# ZYNQ400-MIO.net
KiCad netlist of a schematic drawn in Altium Designer
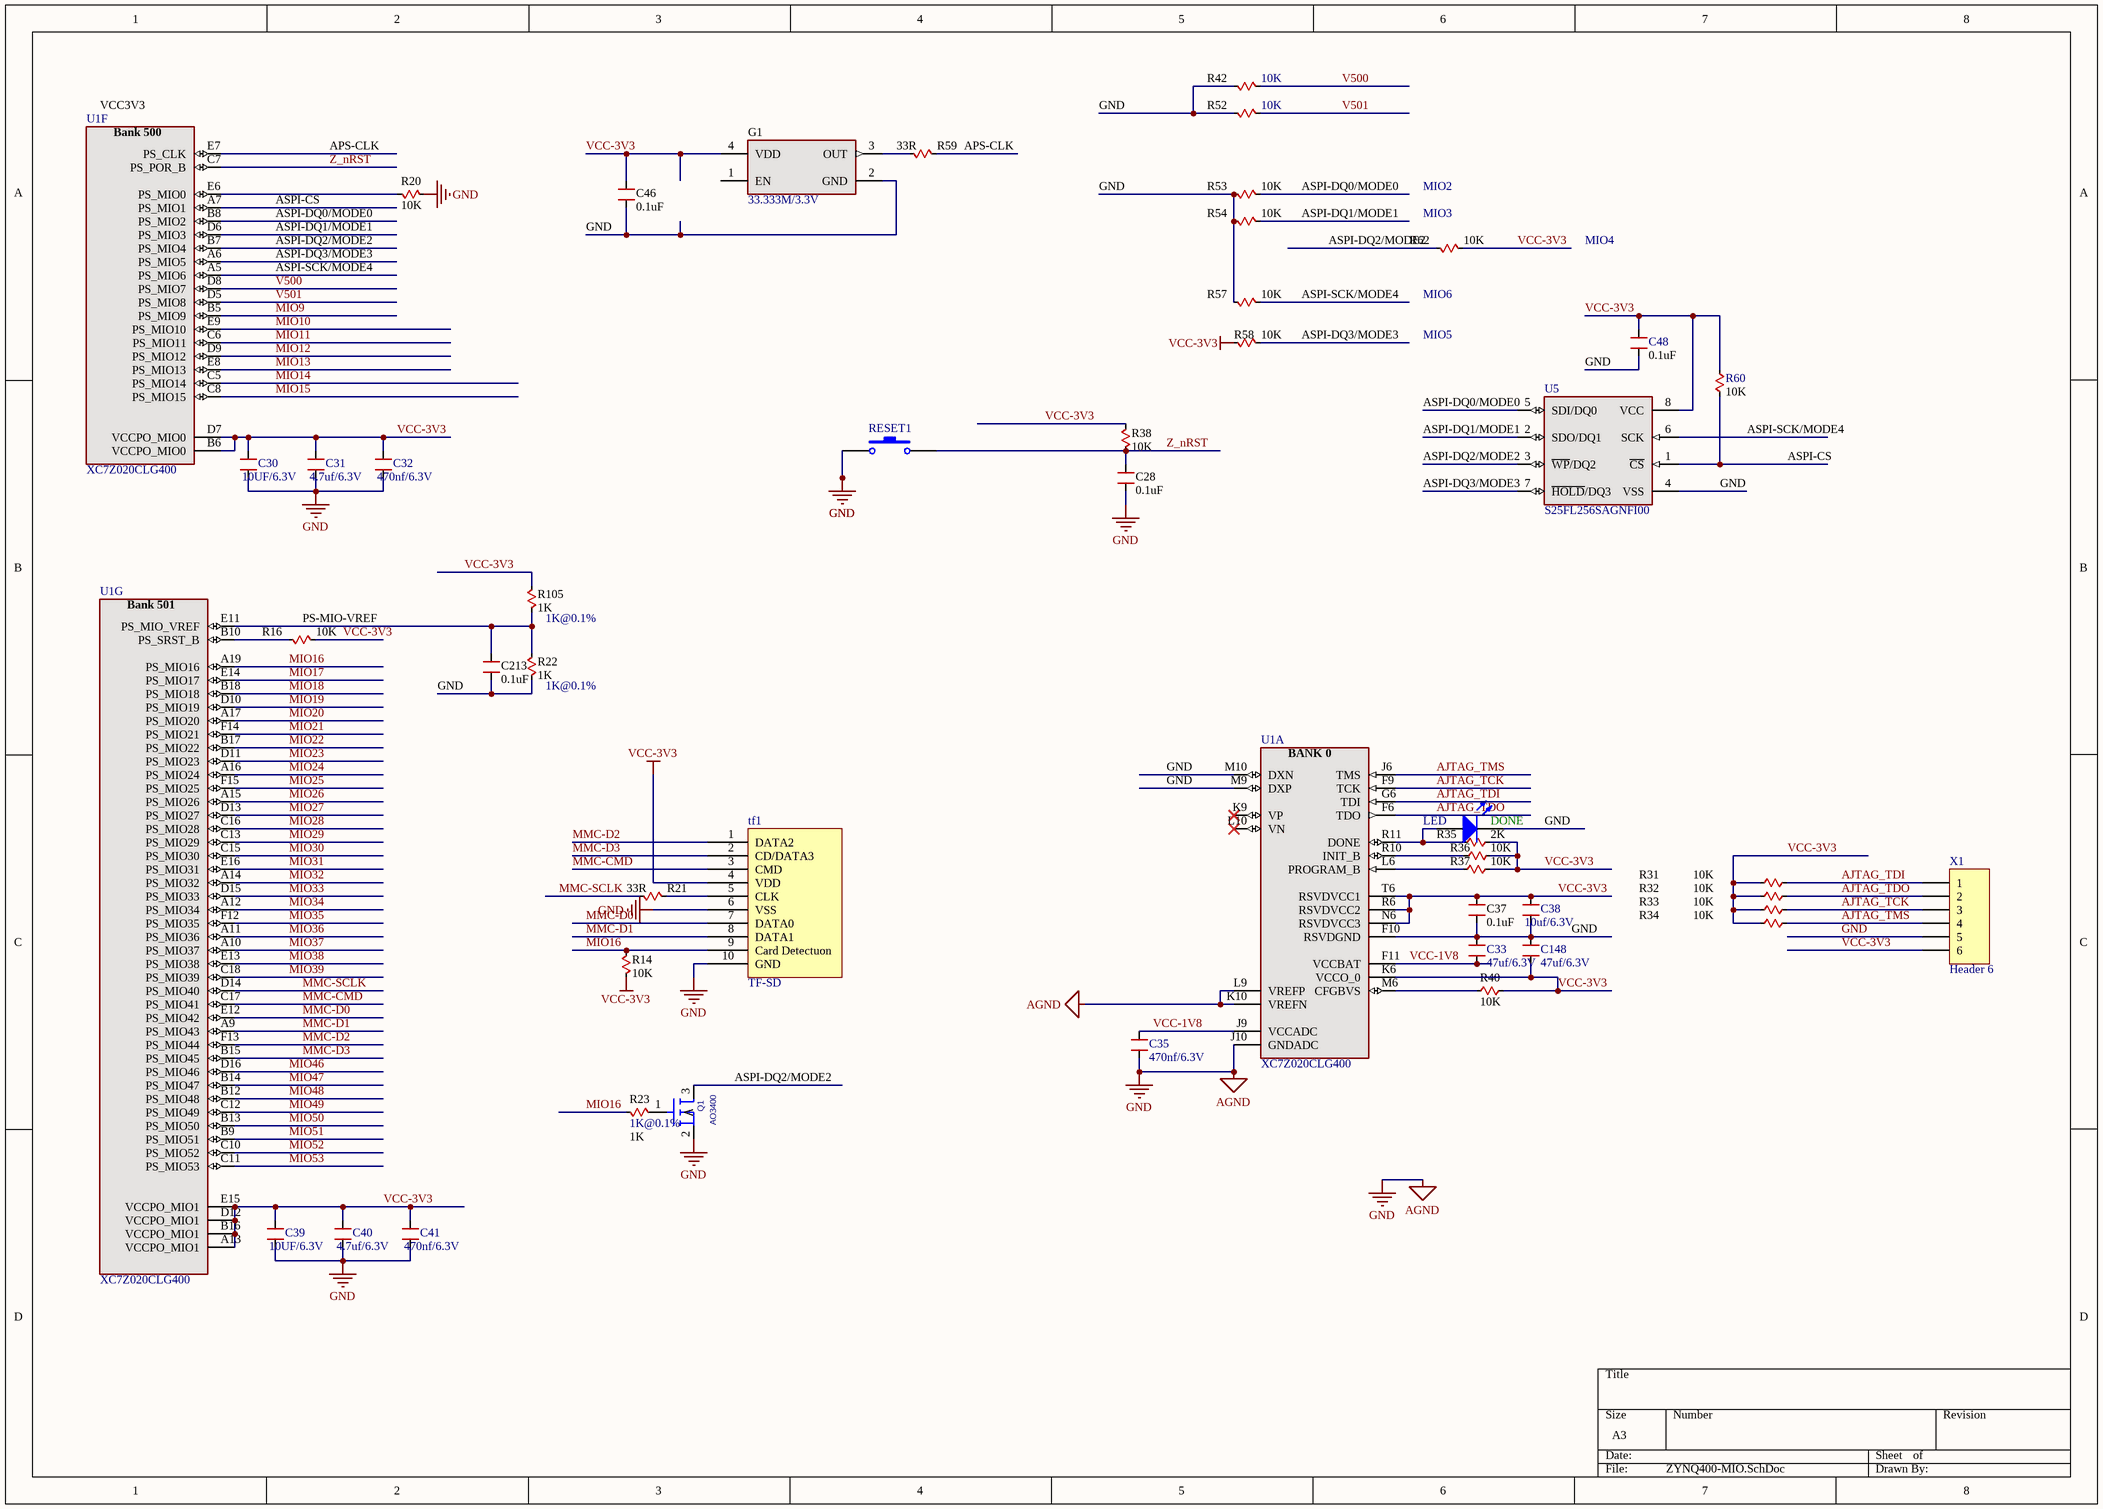
[diagram p0: ZYNQ400-MIO.SchDoc]

(export (version "E")
  (design (tool "Eeschema 10.0.6"))
  (components
    (comp (ref "C28")
      (value "0.1uF")
      (footprint "0402")
      (description "Generic Capacitor")
      (fields (field (name "Comment") "0.1UF"))
      (libsource (lib "Digilent") (part "CAPACITOR"))
    )
    (comp (ref "C30")
      (value "10UF/6.3V")
      (footprint "0402")
      (description "Generic Capacitor")
      (libsource (lib "Digilent") (part "CAPACITOR"))
    )
    (comp (ref "C31")
      (value "4.7uf/6.3V")
      (footprint "0402")
      (description "Generic Capacitor")
      (libsource (lib "Digilent") (part "CAPACITOR"))
    )
    (comp (ref "C32")
      (value "470nf/6.3V")
      (footprint "0402")
      (description "Generic Capacitor")
      (libsource (lib "Digilent") (part "CAPACITOR"))
    )
    (comp (ref "C33")
      (value "47uf/6.3V")
      (footprint "0402")
      (description "Generic Capacitor")
      (libsource (lib "Digilent") (part "CAPACITOR"))
    )
    (comp (ref "C35")
      (value "470nf/6.3V")
      (footprint "0402")
      (description "Generic Capacitor")
      (libsource (lib "Digilent") (part "CAPACITOR"))
    )
    (comp (ref "C37")
      (value "0.1uF")
      (footprint "0402")
      (description "Generic Capacitor")
      (fields (field (name "Comment") "0.1UF"))
      (libsource (lib "Digilent") (part "CAPACITOR"))
    )
    (comp (ref "C38")
      (value "10uf/6.3V")
      (footprint "0603")
      (description "Generic Capacitor")
      (libsource (lib "Digilent") (part "CAPACITOR"))
    )
    (comp (ref "C39")
      (value "10UF/6.3V")
      (footprint "0402")
      (description "Generic Capacitor")
      (libsource (lib "Digilent") (part "CAPACITOR"))
    )
    (comp (ref "C40")
      (value "4.7uf/6.3V")
      (footprint "0402")
      (description "Generic Capacitor")
      (libsource (lib "Digilent") (part "CAPACITOR"))
    )
    (comp (ref "C41")
      (value "470nf/6.3V")
      (footprint "0402")
      (description "Generic Capacitor")
      (libsource (lib "Digilent") (part "CAPACITOR"))
    )
    (comp (ref "C46")
      (value "0.1uF")
      (footprint "0402")
      (description "Generic Capacitor")
      (fields (field (name "Comment") "0.1UF"))
      (libsource (lib "Digilent") (part "CAPACITOR"))
    )
    (comp (ref "C48")
      (value "0.1uF")
      (footprint "0402")
      (description "Generic Capacitor")
      (fields (field (name "Comment") "0.1UF"))
      (libsource (lib "Digilent") (part "CAPACITOR"))
    )
    (comp (ref "C148")
      (value "47uf/6.3V")
      (footprint "0402")
      (description "Generic Capacitor")
      (libsource (lib "Digilent") (part "CAPACITOR"))
    )
    (comp (ref "C213")
      (value "0.1uF")
      (footprint "0402")
      (description "Generic Capacitor")
      (libsource (lib "Digilent") (part "CAPACITOR"))
    )
    (comp (ref "DONE")
      (value "LED")
      (footprint "D0402")
      (description "Typical INFRARED GaAs LED")
      (fields (field (name "PUBLISHER") "Altium Limited"))
      (libsource (lib "Miscellaneous Devices") (part "LED0"))
    )
    (comp (ref "G1")
      (value "33.333M/3.3V")
      (footprint "3.2*2.5")
      (description "3.3V HCMOS Oscillator")
      (fields (field (name "MANUFACTURER") "Fox Electronics"))
      (libsource (lib "Digilent") (part "FXO-HC5"))
    )
    (comp (ref "Q1") (value "AO3400") (footprint "SOT23") (libsource (lib "ZYNQ领航者底板") (part "AO3400")))
    (comp (ref "R14")
      (value "10K")
      (footprint "0402")
      (description "Generic Resistor")
      (libsource (lib "Digilent") (part "RESISTOR"))
    )
    (comp (ref "R16")
      (value "10K")
      (footprint "0402")
      (description "Generic Resistor")
      (libsource (lib "Digilent") (part "RESISTOR"))
    )
    (comp (ref "R20")
      (value "10K")
      (footprint "0402")
      (description "Generic Resistor")
      (libsource (lib "Digilent") (part "RESISTOR"))
    )
    (comp (ref "R21")
      (value "33R")
      (footprint "0402")
      (description "Generic Resistor")
      (libsource (lib "Digilent") (part "RESISTOR"))
    )
    (comp (ref "R22")
      (value "1K@0.1%")
      (footprint "0402")
      (description "Generic Resistor")
      (fields (field (name "ALTIUM_VALUE") "1K"))
      (libsource (lib "Digilent") (part "RESISTOR"))
    )
    (comp (ref "R23")
      (value "1K@0.1%")
      (footprint "0402")
      (description "Generic Resistor")
      (fields (field (name "ALTIUM_VALUE") "1K"))
      (libsource (lib "Digilent") (part "RESISTOR"))
    )
    (comp (ref "R31")
      (value "10K")
      (footprint "0402")
      (description "Generic Resistor")
      (libsource (lib "Digilent") (part "RESISTOR"))
    )
    (comp (ref "R32")
      (value "10K")
      (footprint "0402")
      (description "Generic Resistor")
      (libsource (lib "Digilent") (part "RESISTOR"))
    )
    (comp (ref "R33")
      (value "10K")
      (footprint "0402")
      (description "Generic Resistor")
      (libsource (lib "Digilent") (part "RESISTOR"))
    )
    (comp (ref "R34")
      (value "10K")
      (footprint "0402")
      (description "Generic Resistor")
      (libsource (lib "Digilent") (part "RESISTOR"))
    )
    (comp (ref "R35")
      (value "2K")
      (footprint "0402")
      (description "Generic Resistor")
      (fields (field (name "Comment") "1K"))
      (libsource (lib "Digilent") (part "RESISTOR"))
    )
    (comp (ref "R36")
      (value "10K")
      (footprint "0402")
      (description "Generic Resistor")
      (libsource (lib "Digilent") (part "RESISTOR"))
    )
    (comp (ref "R37")
      (value "10K")
      (footprint "0402")
      (description "Generic Resistor")
      (libsource (lib "Digilent") (part "RESISTOR"))
    )
    (comp (ref "R38")
      (value "10K")
      (footprint "0402")
      (description "Generic Resistor")
      (libsource (lib "Digilent") (part "RESISTOR"))
    )
    (comp (ref "R40")
      (value "10K")
      (footprint "0402")
      (description "Generic Resistor")
      (libsource (lib "Digilent") (part "RESISTOR"))
    )
    (comp (ref "R42")
      (value "10K")
      (footprint "0402")
      (description "Generic Resistor")
      (libsource (lib "Digilent") (part "RESISTOR"))
    )
    (comp (ref "R52")
      (value "10K")
      (footprint "0402")
      (description "Generic Resistor")
      (libsource (lib "Digilent") (part "RESISTOR"))
    )
    (comp (ref "R53")
      (value "10K")
      (footprint "0402")
      (description "Generic Resistor")
      (libsource (lib "Digilent") (part "RESISTOR"))
    )
    (comp (ref "R54")
      (value "10K")
      (footprint "0402")
      (description "Generic Resistor")
      (libsource (lib "Digilent") (part "RESISTOR"))
    )
    (comp (ref "R57")
      (value "10K")
      (footprint "0402")
      (description "Generic Resistor")
      (libsource (lib "Digilent") (part "RESISTOR"))
    )
    (comp (ref "R58")
      (value "10K")
      (footprint "0402")
      (description "Generic Resistor")
      (libsource (lib "Digilent") (part "RESISTOR"))
    )
    (comp (ref "R59")
      (value "33R")
      (footprint "0402")
      (description "Generic Resistor")
      (libsource (lib "Digilent") (part "RESISTOR"))
    )
    (comp (ref "R60")
      (value "10K")
      (footprint "0402")
      (description "Generic Resistor")
      (libsource (lib "Digilent") (part "RESISTOR"))
    )
    (comp (ref "R62")
      (value "10K")
      (footprint "0402")
      (description "Generic Resistor")
      (libsource (lib "Digilent") (part "RESISTOR"))
    )
    (comp (ref "R105")
      (value "1K@0.1%")
      (footprint "0402")
      (description "Generic Resistor")
      (fields (field (name "ALTIUM_VALUE") "1K"))
      (libsource (lib "Digilent") (part "RESISTOR"))
    )
    (comp (ref "RESET1")
      (value "SW-PB")
      (footprint "micro button_2_SMD")
      (description "Switch")
      (fields (field (name "PUBLISHER") "Altium Limited"))
      (libsource (lib "M4(3333)") (part "SW-PB"))
    )
    (comp (ref "tf1") (value "TF-SD") (footprint "TF") (libsource (lib "M4(3333)") (part "TF-SD")))
    (comp (ref "U1")
      (value "XC7Z020CLG400")
      (footprint "CLG400")
      (description "Zynq 7000 FPGA 20 Die, in a CSG 484 Package")
      (fields (field (name "MANUFACTURER") "Xilinx"))
      (libsource (lib "gjws") (part "XC7Z020-CLG400"))
    )
    (comp (ref "U5")
      (value "S25FL256SAGNFI00")
      (footprint "MLP8")
      (description "Serial Flash Memory, 16Mbit, Low Voltage, 50MHz SPI Bus Interface")
      (fields (field (name "MANUFACTURER") "Spansion"))
      (libsource (lib "Digilent") (part "N25Q12-F8"))
    )
    (comp (ref "X1")
      (value "Header 6")
      (footprint "HDR1X6")
      (description "Header, 6-Pin")
      (fields (field (name "PUBLISHER") "Altium Limited"))
      (libsource (lib "Miscellaneous Connectors") (part "Header 6"))
    )
  )
  (nets
    (net (code "1") (name "/AJTAG_TCK") (class "Default")
      (node (ref "R33") (pin "2") (pinfunction "2_2") (pintype "passive"))
      (node (ref "U1") (pin "F9") (pinfunction "TCK_F9") (pintype "input"))
      (node (ref "X1") (pin "3") (pinfunction "3_3") (pintype "passive"))
    )
    (net (code "2") (name "/AJTAG_TDI") (class "Default")
      (node (ref "R31") (pin "2") (pinfunction "2_2") (pintype "passive"))
      (node (ref "U1") (pin "G6") (pinfunction "TDI_G6") (pintype "input"))
      (node (ref "X1") (pin "1") (pinfunction "1_1") (pintype "passive"))
    )
    (net (code "3") (name "/AJTAG_TDO") (class "Default")
      (node (ref "R32") (pin "2") (pinfunction "2_2") (pintype "passive"))
      (node (ref "U1") (pin "F6") (pinfunction "TDO_F6") (pintype "output"))
      (node (ref "X1") (pin "2") (pinfunction "2_2") (pintype "passive"))
    )
    (net (code "4") (name "/AJTAG_TMS") (class "Default")
      (node (ref "R34") (pin "2") (pinfunction "2_2") (pintype "passive"))
      (node (ref "U1") (pin "J6") (pinfunction "TMS_J6") (pintype "input"))
      (node (ref "X1") (pin "4") (pinfunction "4_4") (pintype "passive"))
    )
    (net (code "5") (name "/APS-CLK") (class "Default")
      (node (ref "R59") (pin "2") (pinfunction "2_2") (pintype "passive"))
      (node (ref "U1") (pin "E7") (pinfunction "PS_CLK_E7") (pintype "bidirectional"))
    )
    (net (code "6") (name "/ASPI-CS") (class "Default")
      (node (ref "R60") (pin "2") (pinfunction "2_2") (pintype "passive"))
      (node (ref "U1") (pin "A7") (pinfunction "PS_MIO1_A7") (pintype "bidirectional"))
      (node (ref "U5") (pin "1") (pinfunction "~{CS}_1") (pintype "input"))
    )
    (net (code "7") (name "/ASPI-DQ0{slash}MODE0") (class "Default")
      (node (ref "R53") (pin "2") (pinfunction "2_2") (pintype "passive"))
      (node (ref "U1") (pin "B8") (pinfunction "PS_MIO2_B8") (pintype "bidirectional"))
      (node (ref "U5") (pin "5") (pinfunction "SDI/DQ0_5") (pintype "bidirectional"))
    )
    (net (code "8") (name "/ASPI-DQ1{slash}MODE1") (class "Default")
      (node (ref "R54") (pin "2") (pinfunction "2_2") (pintype "passive"))
      (node (ref "U1") (pin "D6") (pinfunction "PS_MIO3_D6") (pintype "bidirectional"))
      (node (ref "U5") (pin "2") (pinfunction "SDO/DQ1_2") (pintype "bidirectional"))
    )
    (net (code "9") (name "/ASPI-DQ2{slash}MODE2") (class "Default")
      (node (ref "Q1") (pin "3") (pinfunction "D_3") (pintype "passive"))
      (node (ref "R62") (pin "1") (pinfunction "1_1") (pintype "passive"))
      (node (ref "U1") (pin "B7") (pinfunction "PS_MIO4_B7") (pintype "bidirectional"))
      (node (ref "U5") (pin "3") (pinfunction "~{WP}/DQ2_3") (pintype "bidirectional"))
    )
    (net (code "10") (name "/ASPI-DQ3{slash}MODE3") (class "Default")
      (node (ref "R58") (pin "2") (pinfunction "2_2") (pintype "passive"))
      (node (ref "U1") (pin "A6") (pinfunction "PS_MIO5_A6") (pintype "bidirectional"))
      (node (ref "U5") (pin "7") (pinfunction "~{HOLD}/DQ3_7") (pintype "bidirectional"))
    )
    (net (code "11") (name "/ASPI-SCK{slash}MODE4") (class "Default")
      (node (ref "R57") (pin "2") (pinfunction "2_2") (pintype "passive"))
      (node (ref "U1") (pin "A5") (pinfunction "PS_MIO6_A5") (pintype "bidirectional"))
      (node (ref "U5") (pin "6") (pinfunction "SCK_6") (pintype "input"))
    )
    (net (code "12") (name "/MIO9") (class "Default")
      (node (ref "U1") (pin "B5") (pinfunction "PS_MIO9_B5") (pintype "bidirectional"))
    )
    (net (code "13") (name "/MIO10") (class "Default")
      (node (ref "U1") (pin "E9") (pinfunction "PS_MIO10_E9") (pintype "bidirectional"))
    )
    (net (code "14") (name "/MIO11") (class "Default")
      (node (ref "U1") (pin "C6") (pinfunction "PS_MIO11_C6") (pintype "bidirectional"))
    )
    (net (code "15") (name "/MIO12") (class "Default")
      (node (ref "U1") (pin "D9") (pinfunction "PS_MIO12_D9") (pintype "bidirectional"))
    )
    (net (code "16") (name "/MIO13") (class "Default")
      (node (ref "U1") (pin "E8") (pinfunction "PS_MIO13_E8") (pintype "bidirectional"))
    )
    (net (code "17") (name "/MIO14") (class "Default")
      (node (ref "U1") (pin "C5") (pinfunction "PS_MIO14_C5") (pintype "bidirectional"))
    )
    (net (code "18") (name "/MIO15") (class "Default")
      (node (ref "U1") (pin "C8") (pinfunction "PS_MIO15_C8") (pintype "bidirectional"))
    )
    (net (code "19") (name "/MIO16") (class "Default")
      (node (ref "R14") (pin "2") (pinfunction "2_2") (pintype "passive"))
      (node (ref "R23") (pin "1") (pinfunction "1_1") (pintype "passive"))
      (node (ref "U1") (pin "A19") (pinfunction "PS_MIO16_A19") (pintype "bidirectional"))
      (node (ref "tf1") (pin "9") (pinfunction "Card_Detectuon_9") (pintype "passive"))
    )
    (net (code "20") (name "/MIO17") (class "Default")
      (node (ref "U1") (pin "E14") (pinfunction "PS_MIO17_E14") (pintype "bidirectional"))
    )
    (net (code "21") (name "/MIO18") (class "Default")
      (node (ref "U1") (pin "B18") (pinfunction "PS_MIO18_B18") (pintype "bidirectional"))
    )
    (net (code "22") (name "/MIO19") (class "Default")
      (node (ref "U1") (pin "D10") (pinfunction "PS_MIO19_D10") (pintype "bidirectional"))
    )
    (net (code "23") (name "/MIO20") (class "Default")
      (node (ref "U1") (pin "A17") (pinfunction "PS_MIO20_A17") (pintype "bidirectional"))
    )
    (net (code "24") (name "/MIO21") (class "Default")
      (node (ref "U1") (pin "F14") (pinfunction "PS_MIO21_F14") (pintype "bidirectional"))
    )
    (net (code "25") (name "/MIO22") (class "Default")
      (node (ref "U1") (pin "B17") (pinfunction "PS_MIO22_B17") (pintype "bidirectional"))
    )
    (net (code "26") (name "/MIO23") (class "Default")
      (node (ref "U1") (pin "D11") (pinfunction "PS_MIO23_D11") (pintype "bidirectional"))
    )
    (net (code "27") (name "/MIO24") (class "Default")
      (node (ref "U1") (pin "A16") (pinfunction "PS_MIO24_A16") (pintype "bidirectional"))
    )
    (net (code "28") (name "/MIO25") (class "Default")
      (node (ref "U1") (pin "F15") (pinfunction "PS_MIO25_F15") (pintype "bidirectional"))
    )
    (net (code "29") (name "/MIO26") (class "Default")
      (node (ref "U1") (pin "A15") (pinfunction "PS_MIO26_A15") (pintype "bidirectional"))
    )
    (net (code "30") (name "/MIO27") (class "Default")
      (node (ref "U1") (pin "D13") (pinfunction "PS_MIO27_D13") (pintype "bidirectional"))
    )
    (net (code "31") (name "/MIO28") (class "Default")
      (node (ref "U1") (pin "C16") (pinfunction "PS_MIO28_C16") (pintype "bidirectional"))
    )
    (net (code "32") (name "/MIO29") (class "Default")
      (node (ref "U1") (pin "C13") (pinfunction "PS_MIO29_C13") (pintype "bidirectional"))
    )
    (net (code "33") (name "/MIO30") (class "Default")
      (node (ref "U1") (pin "C15") (pinfunction "PS_MIO30_C15") (pintype "bidirectional"))
    )
    (net (code "34") (name "/MIO31") (class "Default")
      (node (ref "U1") (pin "E16") (pinfunction "PS_MIO31_E16") (pintype "bidirectional"))
    )
    (net (code "35") (name "/MIO32") (class "Default")
      (node (ref "U1") (pin "A14") (pinfunction "PS_MIO32_A14") (pintype "bidirectional"))
    )
    (net (code "36") (name "/MIO33") (class "Default")
      (node (ref "U1") (pin "D15") (pinfunction "PS_MIO33_D15") (pintype "bidirectional"))
    )
    (net (code "37") (name "/MIO34") (class "Default")
      (node (ref "U1") (pin "A12") (pinfunction "PS_MIO34_A12") (pintype "bidirectional"))
    )
    (net (code "38") (name "/MIO35") (class "Default")
      (node (ref "U1") (pin "F12") (pinfunction "PS_MIO35_F12") (pintype "bidirectional"))
    )
    (net (code "39") (name "/MIO36") (class "Default")
      (node (ref "U1") (pin "A11") (pinfunction "PS_MIO36_A11") (pintype "bidirectional"))
    )
    (net (code "40") (name "/MIO37") (class "Default")
      (node (ref "U1") (pin "A10") (pinfunction "PS_MIO37_A10") (pintype "bidirectional"))
    )
    (net (code "41") (name "/MIO38") (class "Default")
      (node (ref "U1") (pin "E13") (pinfunction "PS_MIO38_E13") (pintype "bidirectional"))
    )
    (net (code "42") (name "/MIO39") (class "Default")
      (node (ref "U1") (pin "C18") (pinfunction "PS_MIO39_C18") (pintype "bidirectional"))
    )
    (net (code "43") (name "/MIO46") (class "Default")
      (node (ref "U1") (pin "D16") (pinfunction "PS_MIO46_D16") (pintype "bidirectional"))
    )
    (net (code "44") (name "/MIO47") (class "Default")
      (node (ref "U1") (pin "B14") (pinfunction "PS_MIO47_B14") (pintype "bidirectional"))
    )
    (net (code "45") (name "/MIO48") (class "Default")
      (node (ref "U1") (pin "B12") (pinfunction "PS_MIO48_B12") (pintype "bidirectional"))
    )
    (net (code "46") (name "/MIO49") (class "Default")
      (node (ref "U1") (pin "C12") (pinfunction "PS_MIO49_C12") (pintype "bidirectional"))
    )
    (net (code "47") (name "/MIO50") (class "Default")
      (node (ref "U1") (pin "B13") (pinfunction "PS_MIO50_B13") (pintype "bidirectional"))
    )
    (net (code "48") (name "/MIO51") (class "Default")
      (node (ref "U1") (pin "B9") (pinfunction "PS_MIO51_B9") (pintype "bidirectional"))
    )
    (net (code "49") (name "/MIO52") (class "Default")
      (node (ref "U1") (pin "C10") (pinfunction "PS_MIO52_C10") (pintype "bidirectional"))
    )
    (net (code "50") (name "/MIO53") (class "Default")
      (node (ref "U1") (pin "C11") (pinfunction "PS_MIO53_C11") (pintype "bidirectional"))
    )
    (net (code "51") (name "/MMC-CMD") (class "Default")
      (node (ref "U1") (pin "C17") (pinfunction "PS_MIO41_C17") (pintype "bidirectional"))
      (node (ref "tf1") (pin "3") (pinfunction "CMD_3") (pintype "passive"))
    )
    (net (code "52") (name "/MMC-D0") (class "Default")
      (node (ref "U1") (pin "E12") (pinfunction "PS_MIO42_E12") (pintype "bidirectional"))
      (node (ref "tf1") (pin "7") (pinfunction "DATA0_7") (pintype "passive"))
    )
    (net (code "53") (name "/MMC-D1") (class "Default")
      (node (ref "U1") (pin "A9") (pinfunction "PS_MIO43_A9") (pintype "bidirectional"))
      (node (ref "tf1") (pin "8") (pinfunction "DATA1_8") (pintype "passive"))
    )
    (net (code "54") (name "/MMC-D2") (class "Default")
      (node (ref "U1") (pin "F13") (pinfunction "PS_MIO44_F13") (pintype "bidirectional"))
      (node (ref "tf1") (pin "1") (pinfunction "DATA2_1") (pintype "passive"))
    )
    (net (code "55") (name "/MMC-D3") (class "Default")
      (node (ref "U1") (pin "B15") (pinfunction "PS_MIO45_B15") (pintype "bidirectional"))
      (node (ref "tf1") (pin "2") (pinfunction "CD/DATA3_2") (pintype "passive"))
    )
    (net (code "56") (name "/MMC-SCLK") (class "Default")
      (node (ref "R21") (pin "1") (pinfunction "1_1") (pintype "passive"))
      (node (ref "U1") (pin "D14") (pinfunction "PS_MIO40_D14") (pintype "bidirectional"))
    )
    (net (code "57") (name "/PS-MIO-VREF") (class "Default")
      (node (ref "C213") (pin "1") (pinfunction "1_1") (pintype "passive"))
      (node (ref "R105") (pin "2") (pinfunction "2_2") (pintype "passive"))
      (node (ref "R22") (pin "1") (pinfunction "1_1") (pintype "passive"))
      (node (ref "U1") (pin "E11") (pinfunction "PS_MIO_VREF_E11") (pintype "bidirectional"))
    )
    (net (code "58") (name "/V500") (class "Default")
      (node (ref "R42") (pin "2") (pinfunction "2_2") (pintype "passive"))
      (node (ref "U1") (pin "D8") (pinfunction "PS_MIO7_D8") (pintype "bidirectional"))
    )
    (net (code "59") (name "/V501") (class "Default")
      (node (ref "R52") (pin "2") (pinfunction "2_2") (pintype "passive"))
      (node (ref "U1") (pin "D5") (pinfunction "PS_MIO8_D5") (pintype "bidirectional"))
    )
    (net (code "60") (name "/VCC-1V8") (class "Default")
      (node (ref "C33") (pin "1") (pinfunction "1_1") (pintype "passive"))
      (node (ref "C35") (pin "1") (pinfunction "1_1") (pintype "passive"))
      (node (ref "U1") (pin "F11") (pinfunction "VCCBAT_F11") (pintype "passive"))
      (node (ref "U1") (pin "J9") (pinfunction "VCCADC_J9") (pintype "passive"))
    )
    (net (code "61") (name "/Z_nRST") (class "Default")
      (node (ref "C28") (pin "1") (pinfunction "1_1") (pintype "passive"))
      (node (ref "R38") (pin "1") (pinfunction "1_1") (pintype "passive"))
      (node (ref "RESET1") (pin "2") (pinfunction "2_2") (pintype "passive"))
      (node (ref "U1") (pin "C7") (pinfunction "PS_POR_B_C7") (pintype "bidirectional"))
    )
    (net (code "62") (name "AGND") (class "Default")
      (node (ref "C148") (pin "2") (pinfunction "2_2") (pintype "passive"))
      (node (ref "C213") (pin "2") (pinfunction "2_2") (pintype "passive"))
      (node (ref "C28") (pin "2") (pinfunction "2_2") (pintype "passive"))
      (node (ref "C30") (pin "2") (pinfunction "2_2") (pintype "passive"))
      (node (ref "C31") (pin "2") (pinfunction "2_2") (pintype "passive"))
      (node (ref "C32") (pin "2") (pinfunction "2_2") (pintype "passive"))
      (node (ref "C33") (pin "2") (pinfunction "2_2") (pintype "passive"))
      (node (ref "C35") (pin "2") (pinfunction "2_2") (pintype "passive"))
      (node (ref "C37") (pin "2") (pinfunction "2_2") (pintype "passive"))
      (node (ref "C38") (pin "2") (pinfunction "2_2") (pintype "passive"))
      (node (ref "C39") (pin "2") (pinfunction "2_2") (pintype "passive"))
      (node (ref "C40") (pin "2") (pinfunction "2_2") (pintype "passive"))
      (node (ref "C41") (pin "2") (pinfunction "2_2") (pintype "passive"))
      (node (ref "C46") (pin "2") (pinfunction "2_2") (pintype "passive"))
      (node (ref "C48") (pin "2") (pinfunction "2_2") (pintype "passive"))
      (node (ref "DONE") (pin "2") (pinfunction "K_2") (pintype "passive"))
      (node (ref "G1") (pin "2") (pinfunction "GND_2") (pintype "power_in"))
      (node (ref "Q1") (pin "2") (pinfunction "S_2") (pintype "passive"))
      (node (ref "R20") (pin "1") (pinfunction "1_1") (pintype "passive"))
      (node (ref "R22") (pin "2") (pinfunction "2_2") (pintype "passive"))
      (node (ref "R42") (pin "1") (pinfunction "1_1") (pintype "passive"))
      (node (ref "R52") (pin "1") (pinfunction "1_1") (pintype "passive"))
      (node (ref "R53") (pin "1") (pinfunction "1_1") (pintype "passive"))
      (node (ref "R54") (pin "1") (pinfunction "1_1") (pintype "passive"))
      (node (ref "R57") (pin "1") (pinfunction "1_1") (pintype "passive"))
      (node (ref "RESET1") (pin "1") (pinfunction "1_1") (pintype "passive"))
      (node (ref "U1") (pin "F10") (pinfunction "RSVDGND_F10") (pintype "power_in"))
      (node (ref "U1") (pin "J10") (pinfunction "GNDADC_J10") (pintype "passive"))
      (node (ref "U1") (pin "K10") (pinfunction "VREFN_K10") (pintype "passive"))
      (node (ref "U1") (pin "L9") (pinfunction "VREFP_L9") (pintype "passive"))
      (node (ref "U1") (pin "M10") (pinfunction "DXN_M10") (pintype "bidirectional"))
      (node (ref "U1") (pin "M9") (pinfunction "DXP_M9") (pintype "bidirectional"))
      (node (ref "U5") (pin "4") (pinfunction "VSS_4") (pintype "power_in"))
      (node (ref "X1") (pin "5") (pinfunction "5_5") (pintype "passive"))
      (node (ref "tf1") (pin "10") (pinfunction "GND_10") (pintype "passive"))
      (node (ref "tf1") (pin "6") (pinfunction "VSS_6") (pintype "passive"))
    )
    (net (code "63") (name "Net-(DONE-A)") (class "Default")
      (node (ref "DONE") (pin "1") (pinfunction "A_1") (pintype "passive"))
      (node (ref "R35") (pin "1") (pinfunction "1_1") (pintype "passive"))
      (node (ref "U1") (pin "R11") (pinfunction "DONE_R11") (pintype "bidirectional"))
    )
    (net (code "64") (name "Net-(G1-OUT)") (class "Default")
      (node (ref "G1") (pin "3") (pinfunction "OUT_3") (pintype "output"))
      (node (ref "R59") (pin "1") (pinfunction "1_1") (pintype "passive"))
    )
    (net (code "65") (name "Net-(Q1-G)") (class "Default")
      (node (ref "Q1") (pin "1") (pinfunction "G_1") (pintype "passive"))
      (node (ref "R23") (pin "2") (pinfunction "2_2") (pintype "passive"))
    )
    (net (code "66") (name "Net-(U1A-CFGBVS)") (class "Default")
      (node (ref "R40") (pin "1") (pinfunction "1_1") (pintype "passive"))
      (node (ref "U1") (pin "M6") (pinfunction "CFGBVS_M6") (pintype "bidirectional"))
    )
    (net (code "67") (name "Net-(U1A-INIT_B)") (class "Default")
      (node (ref "R36") (pin "2") (pinfunction "2_2") (pintype "passive"))
      (node (ref "U1") (pin "R10") (pinfunction "INIT_B_R10") (pintype "bidirectional"))
    )
    (net (code "68") (name "Net-(U1A-PROGRAM_B)") (class "Default")
      (node (ref "R37") (pin "1") (pinfunction "1_1") (pintype "passive"))
      (node (ref "U1") (pin "L6") (pinfunction "PROGRAM_B_L6") (pintype "input"))
    )
    (net (code "69") (name "Net-(U1F-PS_MIO0)") (class "Default")
      (node (ref "R20") (pin "2") (pinfunction "2_2") (pintype "passive"))
      (node (ref "U1") (pin "E6") (pinfunction "PS_MIO0_E6") (pintype "bidirectional"))
    )
    (net (code "70") (name "Net-(U1G-PS_SRST_B)") (class "Default")
      (node (ref "R16") (pin "1") (pinfunction "1_1") (pintype "passive"))
      (node (ref "U1") (pin "B10") (pinfunction "PS_SRST_B_B10") (pintype "bidirectional"))
    )
    (net (code "71") (name "Net-(tf1-CLK)") (class "Default")
      (node (ref "R21") (pin "2") (pinfunction "2_2") (pintype "passive"))
      (node (ref "tf1") (pin "5") (pinfunction "CLK_5") (pintype "passive"))
    )
    (net (code "72") (name "VCC-3V3") (class "Default")
      (node (ref "C148") (pin "1") (pinfunction "1_1") (pintype "passive"))
      (node (ref "C30") (pin "1") (pinfunction "1_1") (pintype "passive"))
      (node (ref "C31") (pin "1") (pinfunction "1_1") (pintype "passive"))
      (node (ref "C32") (pin "1") (pinfunction "1_1") (pintype "passive"))
      (node (ref "C37") (pin "1") (pinfunction "1_1") (pintype "passive"))
      (node (ref "C38") (pin "1") (pinfunction "1_1") (pintype "passive"))
      (node (ref "C39") (pin "1") (pinfunction "1_1") (pintype "passive"))
      (node (ref "C40") (pin "1") (pinfunction "1_1") (pintype "passive"))
      (node (ref "C41") (pin "1") (pinfunction "1_1") (pintype "passive"))
      (node (ref "C46") (pin "1") (pinfunction "1_1") (pintype "passive"))
      (node (ref "C48") (pin "1") (pinfunction "1_1") (pintype "passive"))
      (node (ref "G1") (pin "4") (pinfunction "VDD_4") (pintype "power_in"))
      (node (ref "R105") (pin "1") (pinfunction "1_1") (pintype "passive"))
      (node (ref "R14") (pin "1") (pinfunction "1_1") (pintype "passive"))
      (node (ref "R16") (pin "2") (pinfunction "2_2") (pintype "passive"))
      (node (ref "R31") (pin "1") (pinfunction "1_1") (pintype "passive"))
      (node (ref "R32") (pin "1") (pinfunction "1_1") (pintype "passive"))
      (node (ref "R33") (pin "1") (pinfunction "1_1") (pintype "passive"))
      (node (ref "R34") (pin "1") (pinfunction "1_1") (pintype "passive"))
      (node (ref "R35") (pin "2") (pinfunction "2_2") (pintype "passive"))
      (node (ref "R36") (pin "1") (pinfunction "1_1") (pintype "passive"))
      (node (ref "R37") (pin "2") (pinfunction "2_2") (pintype "passive"))
      (node (ref "R38") (pin "2") (pinfunction "2_2") (pintype "passive"))
      (node (ref "R40") (pin "2") (pinfunction "2_2") (pintype "passive"))
      (node (ref "R58") (pin "1") (pinfunction "1_1") (pintype "passive"))
      (node (ref "R60") (pin "1") (pinfunction "1_1") (pintype "passive"))
      (node (ref "R62") (pin "2") (pinfunction "2_2") (pintype "passive"))
      (node (ref "U1") (pin "A13") (pinfunction "VCCPO_MIO1_A13") (pintype "power_in"))
      (node (ref "U1") (pin "B16") (pinfunction "VCCPO_MIO1_B16") (pintype "power_in"))
      (node (ref "U1") (pin "B6") (pinfunction "VCCPO_MIO0_B6") (pintype "power_in"))
      (node (ref "U1") (pin "D12") (pinfunction "VCCPO_MIO1_D12") (pintype "power_in"))
      (node (ref "U1") (pin "D7") (pinfunction "VCCPO_MIO0_D7") (pintype "power_in"))
      (node (ref "U1") (pin "E15") (pinfunction "VCCPO_MIO1_E15") (pintype "power_in"))
      (node (ref "U1") (pin "K6") (pinfunction "VCCO_0_K6") (pintype "power_in"))
      (node (ref "U1") (pin "N6") (pinfunction "RSVDVCC3_N6") (pintype "power_in"))
      (node (ref "U1") (pin "R6") (pinfunction "RSVDVCC2_R6") (pintype "power_in"))
      (node (ref "U1") (pin "T6") (pinfunction "RSVDVCC1_T6") (pintype "power_in"))
      (node (ref "U5") (pin "8") (pinfunction "VCC_8") (pintype "power_in"))
      (node (ref "X1") (pin "6") (pinfunction "6_6") (pintype "passive"))
      (node (ref "tf1") (pin "4") (pinfunction "VDD_4") (pintype "passive"))
    )
    (net (code "73") (name "unconnected-(G1-EN-Pad1)") (class "Default")
      (node (ref "G1") (pin "1") (pinfunction "EN_1") (pintype "passive"))
    )
    (net (code "74") (name "unconnected-(U1A-VN-PadL10)") (class "Default")
      (node (ref "U1") (pin "L10") (pinfunction "VN_L10") (pintype "bidirectional+no_connect"))
    )
    (net (code "75") (name "unconnected-(U1A-VP-PadK9)") (class "Default")
      (node (ref "U1") (pin "K9") (pinfunction "VP_K9") (pintype "bidirectional+no_connect"))
    )
  )
)
